# S181X.net
KiCad netlist of a schematic drawn in EAGLE
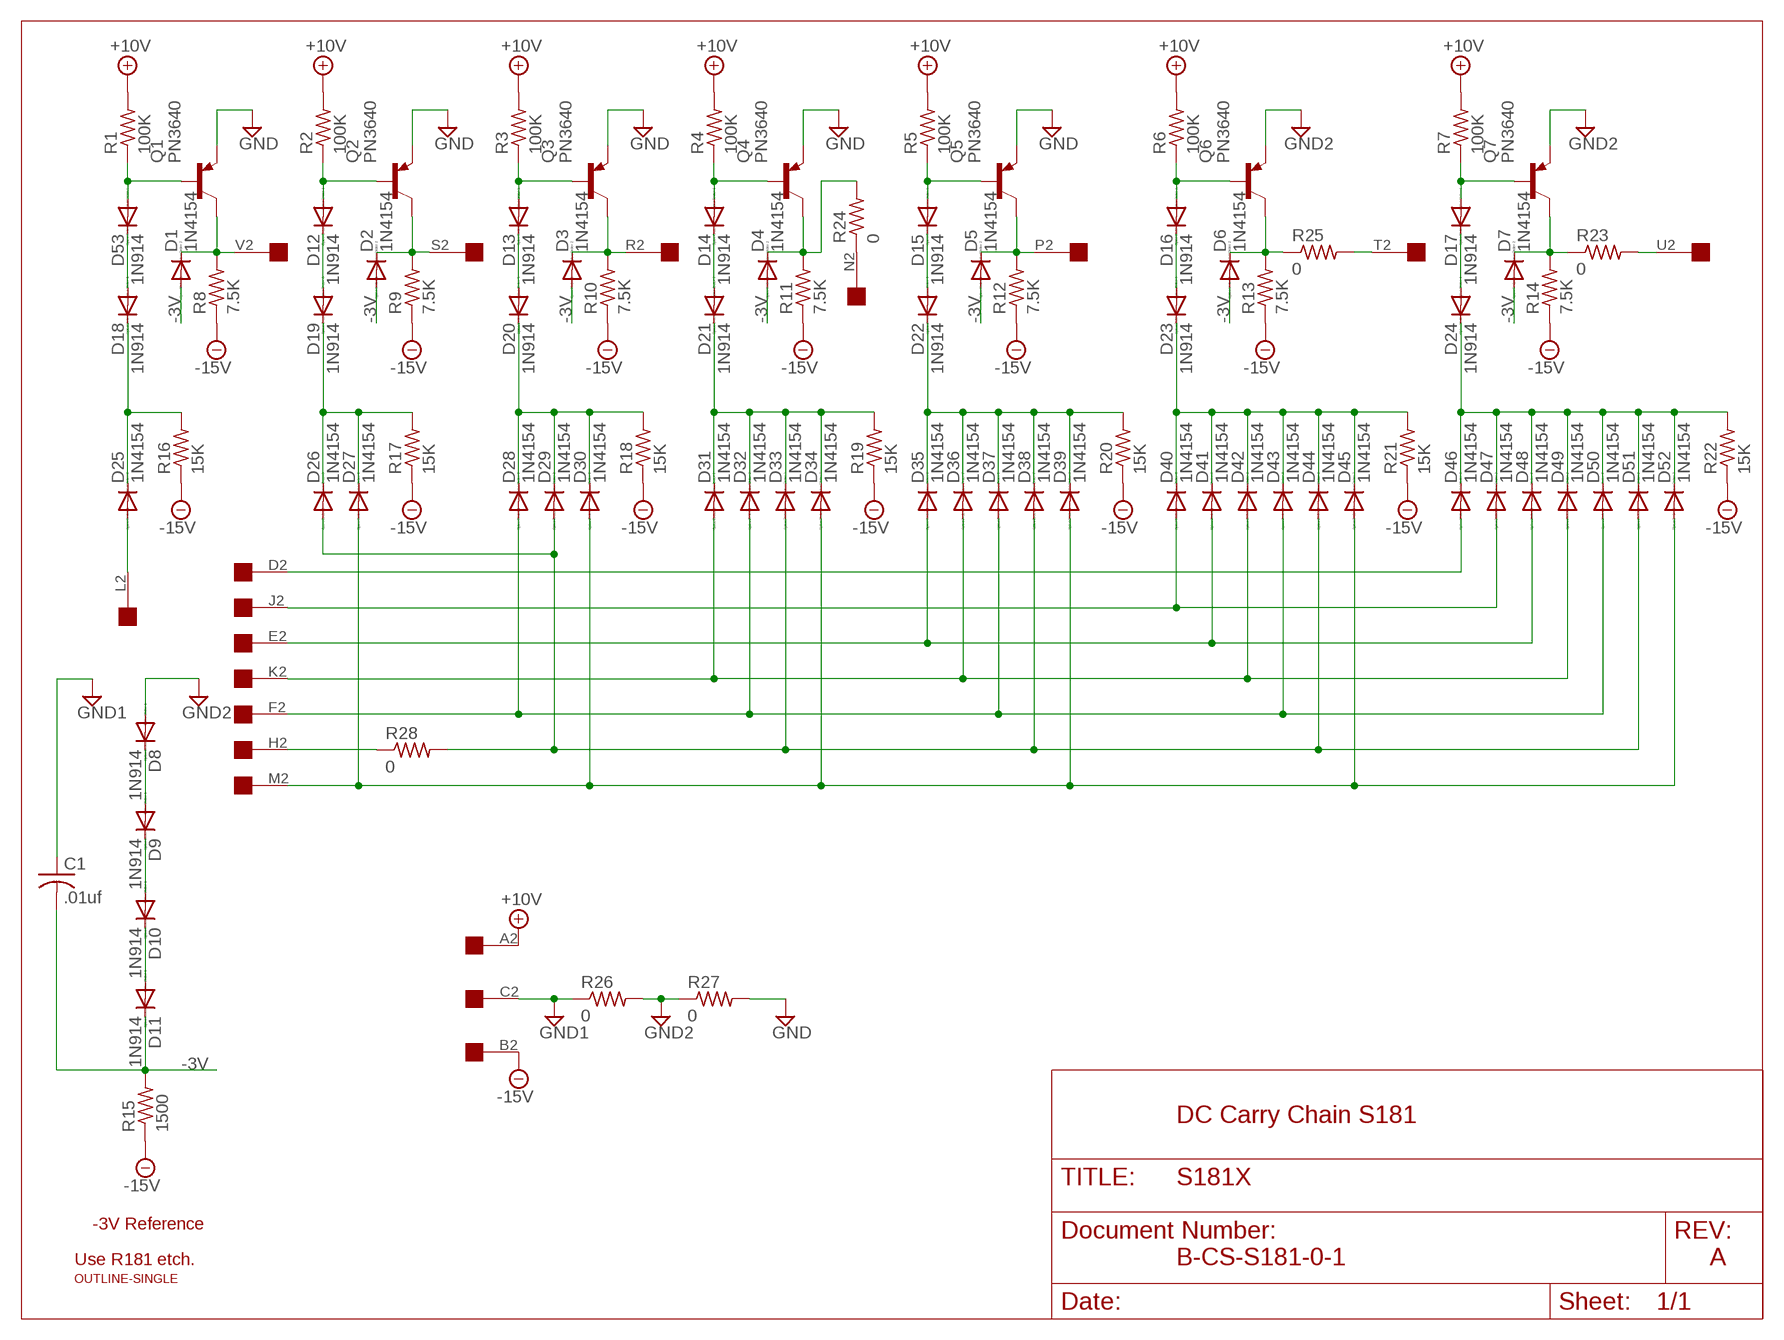
[diagram p0: schematic, sheet 1]

(export (version "E")
  (design (tool "Eeschema 10.0.6"))
  (components
    (comp (ref "C1")
      (value ".01uf")
      (footprint "eagle-import:C050-025X075")
      (libsource (lib "eagle-import") (part "C-US050-025X075"))
    )
    (comp (ref "D1")
      (value "1N4154")
      (footprint "eagle-import:DO35-10")
      (libsource (lib "eagle-import") (part "1N4148DO35-10"))
    )
    (comp (ref "D2")
      (value "1N4154")
      (footprint "eagle-import:DO35-10")
      (libsource (lib "eagle-import") (part "1N4148DO35-10"))
    )
    (comp (ref "D3")
      (value "1N4154")
      (footprint "eagle-import:DO35-10")
      (libsource (lib "eagle-import") (part "1N4148DO35-10"))
    )
    (comp (ref "D4")
      (value "1N4154")
      (footprint "eagle-import:DO35-10")
      (libsource (lib "eagle-import") (part "1N4148DO35-10"))
    )
    (comp (ref "D5")
      (value "1N4154")
      (footprint "eagle-import:DO35-10")
      (libsource (lib "eagle-import") (part "1N4148DO35-10"))
    )
    (comp (ref "D6")
      (value "1N4154")
      (footprint "eagle-import:DO35-10")
      (libsource (lib "eagle-import") (part "1N4148DO35-10"))
    )
    (comp (ref "D7")
      (value "1N4154")
      (footprint "eagle-import:DO35-10")
      (libsource (lib "eagle-import") (part "1N4148DO35-10"))
    )
    (comp (ref "D8")
      (value "1N914")
      (footprint "eagle-import:DO35-10")
      (libsource (lib "eagle-import") (part "1N4148DO35-10"))
    )
    (comp (ref "D9")
      (value "1N914")
      (footprint "eagle-import:DO35-10")
      (libsource (lib "eagle-import") (part "1N4148DO35-10"))
    )
    (comp (ref "D10")
      (value "1N914")
      (footprint "eagle-import:DO35-10")
      (libsource (lib "eagle-import") (part "1N4148DO35-10"))
    )
    (comp (ref "D11")
      (value "1N914")
      (footprint "eagle-import:DO35-10")
      (libsource (lib "eagle-import") (part "1N4148DO35-10"))
    )
    (comp (ref "D12")
      (value "1N914")
      (footprint "eagle-import:DO35-10")
      (libsource (lib "eagle-import") (part "1N4148DO35-10"))
    )
    (comp (ref "D13")
      (value "1N914")
      (footprint "eagle-import:DO35-10")
      (libsource (lib "eagle-import") (part "1N4148DO35-10"))
    )
    (comp (ref "D14")
      (value "1N914")
      (footprint "eagle-import:DO35-10")
      (libsource (lib "eagle-import") (part "1N4148DO35-10"))
    )
    (comp (ref "D15")
      (value "1N914")
      (footprint "eagle-import:DO35-10")
      (libsource (lib "eagle-import") (part "1N4148DO35-10"))
    )
    (comp (ref "D16")
      (value "1N914")
      (footprint "eagle-import:DO35-10")
      (libsource (lib "eagle-import") (part "1N4148DO35-10"))
    )
    (comp (ref "D17")
      (value "1N914")
      (footprint "eagle-import:DO35-10")
      (libsource (lib "eagle-import") (part "1N4148DO35-10"))
    )
    (comp (ref "D18")
      (value "1N914")
      (footprint "eagle-import:DO35-10")
      (libsource (lib "eagle-import") (part "1N4148DO35-10"))
    )
    (comp (ref "D19")
      (value "1N914")
      (footprint "eagle-import:DO35-10")
      (libsource (lib "eagle-import") (part "1N4148DO35-10"))
    )
    (comp (ref "D20")
      (value "1N914")
      (footprint "eagle-import:DO35-10")
      (libsource (lib "eagle-import") (part "1N4148DO35-10"))
    )
    (comp (ref "D21")
      (value "1N914")
      (footprint "eagle-import:DO35-10")
      (libsource (lib "eagle-import") (part "1N4148DO35-10"))
    )
    (comp (ref "D22")
      (value "1N914")
      (footprint "eagle-import:DO35-10")
      (libsource (lib "eagle-import") (part "1N4148DO35-10"))
    )
    (comp (ref "D23")
      (value "1N914")
      (footprint "eagle-import:DO35-10")
      (libsource (lib "eagle-import") (part "1N4148DO35-10"))
    )
    (comp (ref "D24")
      (value "1N914")
      (footprint "eagle-import:DO35-10")
      (libsource (lib "eagle-import") (part "1N4148DO35-10"))
    )
    (comp (ref "D25")
      (value "1N4154")
      (footprint "eagle-import:DO35-10")
      (libsource (lib "eagle-import") (part "1N4148DO35-10"))
    )
    (comp (ref "D26")
      (value "1N4154")
      (footprint "eagle-import:DO35-10")
      (libsource (lib "eagle-import") (part "1N4148DO35-10"))
    )
    (comp (ref "D27")
      (value "1N4154")
      (footprint "eagle-import:DO35-10")
      (libsource (lib "eagle-import") (part "1N4148DO35-10"))
    )
    (comp (ref "D28")
      (value "1N4154")
      (footprint "eagle-import:DO35-10")
      (libsource (lib "eagle-import") (part "1N4148DO35-10"))
    )
    (comp (ref "D29")
      (value "1N4154")
      (footprint "eagle-import:DO35-10")
      (libsource (lib "eagle-import") (part "1N4148DO35-10"))
    )
    (comp (ref "D30")
      (value "1N4154")
      (footprint "eagle-import:DO35-10")
      (libsource (lib "eagle-import") (part "1N4148DO35-10"))
    )
    (comp (ref "D31")
      (value "1N4154")
      (footprint "eagle-import:DO35-10")
      (libsource (lib "eagle-import") (part "1N4148DO35-10"))
    )
    (comp (ref "D32")
      (value "1N4154")
      (footprint "eagle-import:DO35-10")
      (libsource (lib "eagle-import") (part "1N4148DO35-10"))
    )
    (comp (ref "D33")
      (value "1N4154")
      (footprint "eagle-import:DO35-10")
      (libsource (lib "eagle-import") (part "1N4148DO35-10"))
    )
    (comp (ref "D34")
      (value "1N4154")
      (footprint "eagle-import:DO35-10")
      (libsource (lib "eagle-import") (part "1N4148DO35-10"))
    )
    (comp (ref "D35")
      (value "1N4154")
      (footprint "eagle-import:DO35-10")
      (libsource (lib "eagle-import") (part "1N4148DO35-10"))
    )
    (comp (ref "D36")
      (value "1N4154")
      (footprint "eagle-import:DO35-10")
      (libsource (lib "eagle-import") (part "1N4148DO35-10"))
    )
    (comp (ref "D37")
      (value "1N4154")
      (footprint "eagle-import:DO35-10")
      (libsource (lib "eagle-import") (part "1N4148DO35-10"))
    )
    (comp (ref "D38")
      (value "1N4154")
      (footprint "eagle-import:DO35-10")
      (libsource (lib "eagle-import") (part "1N4148DO35-10"))
    )
    (comp (ref "D39")
      (value "1N4154")
      (footprint "eagle-import:DO35-10")
      (libsource (lib "eagle-import") (part "1N4148DO35-10"))
    )
    (comp (ref "D40")
      (value "1N4154")
      (footprint "eagle-import:DO35-10")
      (libsource (lib "eagle-import") (part "1N4148DO35-10"))
    )
    (comp (ref "D41")
      (value "1N4154")
      (footprint "eagle-import:DO35-10")
      (libsource (lib "eagle-import") (part "1N4148DO35-10"))
    )
    (comp (ref "D42")
      (value "1N4154")
      (footprint "eagle-import:DO35-10")
      (libsource (lib "eagle-import") (part "1N4148DO35-10"))
    )
    (comp (ref "D43")
      (value "1N4154")
      (footprint "eagle-import:DO35-10")
      (libsource (lib "eagle-import") (part "1N4148DO35-10"))
    )
    (comp (ref "D44")
      (value "1N4154")
      (footprint "eagle-import:DO35-10")
      (libsource (lib "eagle-import") (part "1N4148DO35-10"))
    )
    (comp (ref "D45")
      (value "1N4154")
      (footprint "eagle-import:DO35-10")
      (libsource (lib "eagle-import") (part "1N4148DO35-10"))
    )
    (comp (ref "D46")
      (value "1N4154")
      (footprint "eagle-import:DO35-10")
      (libsource (lib "eagle-import") (part "1N4148DO35-10"))
    )
    (comp (ref "D47")
      (value "1N4154")
      (footprint "eagle-import:DO35-10")
      (libsource (lib "eagle-import") (part "1N4148DO35-10"))
    )
    (comp (ref "D48")
      (value "1N4154")
      (footprint "eagle-import:DO35-10")
      (libsource (lib "eagle-import") (part "1N4148DO35-10"))
    )
    (comp (ref "D49")
      (value "1N4154")
      (footprint "eagle-import:DO35-10")
      (libsource (lib "eagle-import") (part "1N4148DO35-10"))
    )
    (comp (ref "D50")
      (value "1N4154")
      (footprint "eagle-import:DO35-10")
      (libsource (lib "eagle-import") (part "1N4148DO35-10"))
    )
    (comp (ref "D51")
      (value "1N4154")
      (footprint "eagle-import:DO35-10")
      (libsource (lib "eagle-import") (part "1N4148DO35-10"))
    )
    (comp (ref "D52")
      (value "1N4154")
      (footprint "eagle-import:DO35-10")
      (libsource (lib "eagle-import") (part "1N4148DO35-10"))
    )
    (comp (ref "D53")
      (value "1N914")
      (footprint "eagle-import:DO35-10")
      (libsource (lib "eagle-import") (part "1N4148DO35-10"))
    )
    (comp (ref "Q1")
      (value "PN3640")
      (footprint "eagle-import:TO39")
      (libsource (lib "eagle-import") (part "2N3637"))
    )
    (comp (ref "Q2")
      (value "PN3640")
      (footprint "eagle-import:TO39")
      (libsource (lib "eagle-import") (part "2N3637"))
    )
    (comp (ref "Q3")
      (value "PN3640")
      (footprint "eagle-import:TO39")
      (libsource (lib "eagle-import") (part "2N3637"))
    )
    (comp (ref "Q4")
      (value "PN3640")
      (footprint "eagle-import:TO39")
      (libsource (lib "eagle-import") (part "2N3637"))
    )
    (comp (ref "Q5")
      (value "PN3640")
      (footprint "eagle-import:TO39")
      (libsource (lib "eagle-import") (part "2N3637"))
    )
    (comp (ref "Q6")
      (value "PN3640")
      (footprint "eagle-import:TO39")
      (libsource (lib "eagle-import") (part "2N3637"))
    )
    (comp (ref "Q7")
      (value "PN3640")
      (footprint "eagle-import:TO39")
      (libsource (lib "eagle-import") (part "2N3637"))
    )
    (comp (ref "R1")
      (value "100K")
      (footprint "eagle-import:0207_10")
      (libsource (lib "eagle-import") (part "R-US_0207/10"))
    )
    (comp (ref "R2")
      (value "100K")
      (footprint "eagle-import:0207_10")
      (libsource (lib "eagle-import") (part "R-US_0207/10"))
    )
    (comp (ref "R3")
      (value "100K")
      (footprint "eagle-import:0207_10")
      (libsource (lib "eagle-import") (part "R-US_0207/10"))
    )
    (comp (ref "R4")
      (value "100K")
      (footprint "eagle-import:0207_10")
      (libsource (lib "eagle-import") (part "R-US_0207/10"))
    )
    (comp (ref "R5")
      (value "100K")
      (footprint "eagle-import:0207_10")
      (libsource (lib "eagle-import") (part "R-US_0207/10"))
    )
    (comp (ref "R6")
      (value "100K")
      (footprint "eagle-import:0207_10")
      (libsource (lib "eagle-import") (part "R-US_0207/10"))
    )
    (comp (ref "R7")
      (value "100K")
      (footprint "eagle-import:0207_10")
      (libsource (lib "eagle-import") (part "R-US_0207/10"))
    )
    (comp (ref "R8")
      (value "7.5K")
      (footprint "eagle-import:0207_10")
      (libsource (lib "eagle-import") (part "R-US_0207/10"))
    )
    (comp (ref "R9")
      (value "7.5K")
      (footprint "eagle-import:0207_10")
      (libsource (lib "eagle-import") (part "R-US_0207/10"))
    )
    (comp (ref "R10")
      (value "7.5K")
      (footprint "eagle-import:0207_10")
      (libsource (lib "eagle-import") (part "R-US_0207/10"))
    )
    (comp (ref "R11")
      (value "7.5K")
      (footprint "eagle-import:0207_10")
      (libsource (lib "eagle-import") (part "R-US_0207/10"))
    )
    (comp (ref "R12")
      (value "7.5K")
      (footprint "eagle-import:0207_10")
      (libsource (lib "eagle-import") (part "R-US_0207/10"))
    )
    (comp (ref "R13")
      (value "7.5K")
      (footprint "eagle-import:0207_10")
      (libsource (lib "eagle-import") (part "R-US_0207/10"))
    )
    (comp (ref "R14")
      (value "7.5K")
      (footprint "eagle-import:0207_10")
      (libsource (lib "eagle-import") (part "R-US_0207/10"))
    )
    (comp (ref "R15")
      (value "1500")
      (footprint "eagle-import:0207_10")
      (libsource (lib "eagle-import") (part "R-US_0207/10"))
    )
    (comp (ref "R16")
      (value "15K")
      (footprint "eagle-import:0207_10")
      (libsource (lib "eagle-import") (part "R-US_0207/10"))
    )
    (comp (ref "R17")
      (value "15K")
      (footprint "eagle-import:0207_10")
      (libsource (lib "eagle-import") (part "R-US_0207/10"))
    )
    (comp (ref "R18")
      (value "15K")
      (footprint "eagle-import:0207_10")
      (libsource (lib "eagle-import") (part "R-US_0207/10"))
    )
    (comp (ref "R19")
      (value "15K")
      (footprint "eagle-import:0207_10")
      (libsource (lib "eagle-import") (part "R-US_0207/10"))
    )
    (comp (ref "R20")
      (value "15K")
      (footprint "eagle-import:0207_10")
      (libsource (lib "eagle-import") (part "R-US_0207/10"))
    )
    (comp (ref "R21")
      (value "15K")
      (footprint "eagle-import:0207_10")
      (libsource (lib "eagle-import") (part "R-US_0207/10"))
    )
    (comp (ref "R22")
      (value "15K")
      (footprint "eagle-import:0207_10")
      (libsource (lib "eagle-import") (part "R-US_0207/10"))
    )
    (comp (ref "R23")
      (value "0")
      (footprint "eagle-import:0207_10")
      (libsource (lib "eagle-import") (part "R-US_0207/10"))
    )
    (comp (ref "R24")
      (value "0")
      (footprint "eagle-import:0207_10")
      (libsource (lib "eagle-import") (part "R-US_0207/10"))
    )
    (comp (ref "R25")
      (value "0")
      (footprint "eagle-import:0207_10")
      (libsource (lib "eagle-import") (part "R-US_0207/10"))
    )
    (comp (ref "R26")
      (value "0")
      (footprint "eagle-import:0207_10")
      (libsource (lib "eagle-import") (part "R-US_0207/10"))
    )
    (comp (ref "R27")
      (value "0")
      (footprint "eagle-import:0207_10")
      (libsource (lib "eagle-import") (part "R-US_0207/10"))
    )
    (comp (ref "R28")
      (value "0")
      (footprint "eagle-import:0207_10")
      (libsource (lib "eagle-import") (part "R-US_0207/10"))
    )
    (comp (ref "U$1")
      (value "OUTLINE-SINGLE")
      (footprint "eagle-import:SINGLE")
      (libsource (lib "eagle-import") (part "OUTLINE-SINGLE"))
    )
    (comp (ref "U$2")
      (value "EDGE-1")
      (footprint "eagle-import:EDGE-CON1")
      (libsource (lib "eagle-import") (part "EDGE-1"))
    )
  )
  (nets
    (net (code "1") (name "+10V") (class "Default")
      (node (ref "R1") (pin "2") (pinfunction "2_2") (pintype "passive"))
      (node (ref "R2") (pin "2") (pinfunction "2_2") (pintype "passive"))
      (node (ref "R3") (pin "2") (pinfunction "2_2") (pintype "passive"))
      (node (ref "R4") (pin "2") (pinfunction "2_2") (pintype "passive"))
      (node (ref "R5") (pin "2") (pinfunction "2_2") (pintype "passive"))
      (node (ref "R6") (pin "2") (pinfunction "2_2") (pintype "passive"))
      (node (ref "R7") (pin "2") (pinfunction "2_2") (pintype "passive"))
      (node (ref "U$2") (pin "A2") (pinfunction "1_A2") (pintype "bidirectional"))
    )
    (net (code "2") (name "-15V") (class "Default")
      (node (ref "R10") (pin "1") (pinfunction "1_1") (pintype "passive"))
      (node (ref "R11") (pin "1") (pinfunction "1_1") (pintype "passive"))
      (node (ref "R12") (pin "1") (pinfunction "1_1") (pintype "passive"))
      (node (ref "R13") (pin "1") (pinfunction "1_1") (pintype "passive"))
      (node (ref "R14") (pin "1") (pinfunction "1_1") (pintype "passive"))
      (node (ref "R15") (pin "1") (pinfunction "1_1") (pintype "passive"))
      (node (ref "R16") (pin "1") (pinfunction "1_1") (pintype "passive"))
      (node (ref "R17") (pin "1") (pinfunction "1_1") (pintype "passive"))
      (node (ref "R18") (pin "1") (pinfunction "1_1") (pintype "passive"))
      (node (ref "R19") (pin "1") (pinfunction "1_1") (pintype "passive"))
      (node (ref "R20") (pin "1") (pinfunction "1_1") (pintype "passive"))
      (node (ref "R21") (pin "1") (pinfunction "1_1") (pintype "passive"))
      (node (ref "R22") (pin "1") (pinfunction "1_1") (pintype "passive"))
      (node (ref "R8") (pin "1") (pinfunction "1_1") (pintype "passive"))
      (node (ref "R9") (pin "1") (pinfunction "1_1") (pintype "passive"))
      (node (ref "U$2") (pin "B2") (pinfunction "1_B2") (pintype "bidirectional"))
    )
    (net (code "3") (name "/-3V") (class "Default")
      (node (ref "C1") (pin "2") (pinfunction "2_2") (pintype "passive"))
      (node (ref "D1") (pin "A") (pinfunction "A_A") (pintype "passive"))
      (node (ref "D11") (pin "C") (pinfunction "C_C") (pintype "passive"))
      (node (ref "D2") (pin "A") (pinfunction "A_A") (pintype "passive"))
      (node (ref "D3") (pin "A") (pinfunction "A_A") (pintype "passive"))
      (node (ref "D4") (pin "A") (pinfunction "A_A") (pintype "passive"))
      (node (ref "D5") (pin "A") (pinfunction "A_A") (pintype "passive"))
      (node (ref "D6") (pin "A") (pinfunction "A_A") (pintype "passive"))
      (node (ref "D7") (pin "A") (pinfunction "A_A") (pintype "passive"))
      (node (ref "R15") (pin "2") (pinfunction "2_2") (pintype "passive"))
    )
    (net (code "4") (name "GND") (class "Default")
      (node (ref "Q1") (pin "1") (pinfunction "E_1") (pintype "passive"))
      (node (ref "Q2") (pin "1") (pinfunction "E_1") (pintype "passive"))
      (node (ref "Q3") (pin "1") (pinfunction "E_1") (pintype "passive"))
      (node (ref "Q4") (pin "1") (pinfunction "E_1") (pintype "passive"))
      (node (ref "Q5") (pin "1") (pinfunction "E_1") (pintype "passive"))
      (node (ref "R27") (pin "2") (pinfunction "2_2") (pintype "passive"))
    )
    (net (code "5") (name "GND1") (class "Default")
      (node (ref "C1") (pin "1") (pinfunction "1_1") (pintype "passive"))
      (node (ref "R26") (pin "1") (pinfunction "1_1") (pintype "passive"))
      (node (ref "U$2") (pin "C2") (pinfunction "1_C2") (pintype "bidirectional"))
    )
    (net (code "6") (name "GND2") (class "Default")
      (node (ref "D8") (pin "A") (pinfunction "A_A") (pintype "passive"))
      (node (ref "Q6") (pin "1") (pinfunction "E_1") (pintype "passive"))
      (node (ref "Q7") (pin "1") (pinfunction "E_1") (pintype "passive"))
      (node (ref "R26") (pin "2") (pinfunction "2_2") (pintype "passive"))
      (node (ref "R27") (pin "1") (pinfunction "1_1") (pintype "passive"))
    )
    (net (code "7") (name "Net-(D8-PadC)") (class "Default")
      (node (ref "D8") (pin "C") (pinfunction "C_C") (pintype "passive"))
      (node (ref "D9") (pin "A") (pinfunction "A_A") (pintype "passive"))
    )
    (net (code "8") (name "Net-(D10-PadA)") (class "Default")
      (node (ref "D10") (pin "A") (pinfunction "A_A") (pintype "passive"))
      (node (ref "D9") (pin "C") (pinfunction "C_C") (pintype "passive"))
    )
    (net (code "9") (name "Net-(D10-PadC)") (class "Default")
      (node (ref "D10") (pin "C") (pinfunction "C_C") (pintype "passive"))
      (node (ref "D11") (pin "A") (pinfunction "A_A") (pintype "passive"))
    )
    (net (code "10") (name "Net-(D12-PadC)") (class "Default")
      (node (ref "D12") (pin "C") (pinfunction "C_C") (pintype "passive"))
      (node (ref "D19") (pin "A") (pinfunction "A_A") (pintype "passive"))
    )
    (net (code "11") (name "Net-(D13-PadC)") (class "Default")
      (node (ref "D13") (pin "C") (pinfunction "C_C") (pintype "passive"))
      (node (ref "D20") (pin "A") (pinfunction "A_A") (pintype "passive"))
    )
    (net (code "12") (name "Net-(D14-PadC)") (class "Default")
      (node (ref "D14") (pin "C") (pinfunction "C_C") (pintype "passive"))
      (node (ref "D21") (pin "A") (pinfunction "A_A") (pintype "passive"))
    )
    (net (code "13") (name "Net-(D15-PadC)") (class "Default")
      (node (ref "D15") (pin "C") (pinfunction "C_C") (pintype "passive"))
      (node (ref "D22") (pin "A") (pinfunction "A_A") (pintype "passive"))
    )
    (net (code "14") (name "Net-(D16-PadC)") (class "Default")
      (node (ref "D16") (pin "C") (pinfunction "C_C") (pintype "passive"))
      (node (ref "D23") (pin "A") (pinfunction "A_A") (pintype "passive"))
    )
    (net (code "15") (name "Net-(D17-PadC)") (class "Default")
      (node (ref "D17") (pin "C") (pinfunction "C_C") (pintype "passive"))
      (node (ref "D24") (pin "A") (pinfunction "A_A") (pintype "passive"))
    )
    (net (code "16") (name "Net-(D18-PadA)") (class "Default")
      (node (ref "D18") (pin "A") (pinfunction "A_A") (pintype "passive"))
      (node (ref "D53") (pin "C") (pinfunction "C_C") (pintype "passive"))
    )
    (net (code "17") (name "Net-(D18-PadC)") (class "Default")
      (node (ref "D18") (pin "C") (pinfunction "C_C") (pintype "passive"))
      (node (ref "D25") (pin "C") (pinfunction "C_C") (pintype "passive"))
      (node (ref "R16") (pin "2") (pinfunction "2_2") (pintype "passive"))
    )
    (net (code "18") (name "Net-(D19-PadC)") (class "Default")
      (node (ref "D19") (pin "C") (pinfunction "C_C") (pintype "passive"))
      (node (ref "D26") (pin "C") (pinfunction "C_C") (pintype "passive"))
      (node (ref "D27") (pin "C") (pinfunction "C_C") (pintype "passive"))
      (node (ref "R17") (pin "2") (pinfunction "2_2") (pintype "passive"))
    )
    (net (code "19") (name "Net-(D20-PadC)") (class "Default")
      (node (ref "D20") (pin "C") (pinfunction "C_C") (pintype "passive"))
      (node (ref "D28") (pin "C") (pinfunction "C_C") (pintype "passive"))
      (node (ref "D29") (pin "C") (pinfunction "C_C") (pintype "passive"))
      (node (ref "D30") (pin "C") (pinfunction "C_C") (pintype "passive"))
      (node (ref "R18") (pin "2") (pinfunction "2_2") (pintype "passive"))
    )
    (net (code "20") (name "Net-(D21-PadC)") (class "Default")
      (node (ref "D21") (pin "C") (pinfunction "C_C") (pintype "passive"))
      (node (ref "D31") (pin "C") (pinfunction "C_C") (pintype "passive"))
      (node (ref "D32") (pin "C") (pinfunction "C_C") (pintype "passive"))
      (node (ref "D33") (pin "C") (pinfunction "C_C") (pintype "passive"))
      (node (ref "D34") (pin "C") (pinfunction "C_C") (pintype "passive"))
      (node (ref "R19") (pin "2") (pinfunction "2_2") (pintype "passive"))
    )
    (net (code "21") (name "Net-(D22-PadC)") (class "Default")
      (node (ref "D22") (pin "C") (pinfunction "C_C") (pintype "passive"))
      (node (ref "D35") (pin "C") (pinfunction "C_C") (pintype "passive"))
      (node (ref "D36") (pin "C") (pinfunction "C_C") (pintype "passive"))
      (node (ref "D37") (pin "C") (pinfunction "C_C") (pintype "passive"))
      (node (ref "D38") (pin "C") (pinfunction "C_C") (pintype "passive"))
      (node (ref "D39") (pin "C") (pinfunction "C_C") (pintype "passive"))
      (node (ref "R20") (pin "2") (pinfunction "2_2") (pintype "passive"))
    )
    (net (code "22") (name "Net-(D23-PadC)") (class "Default")
      (node (ref "D23") (pin "C") (pinfunction "C_C") (pintype "passive"))
      (node (ref "D40") (pin "C") (pinfunction "C_C") (pintype "passive"))
      (node (ref "D41") (pin "C") (pinfunction "C_C") (pintype "passive"))
      (node (ref "D42") (pin "C") (pinfunction "C_C") (pintype "passive"))
      (node (ref "D43") (pin "C") (pinfunction "C_C") (pintype "passive"))
      (node (ref "D44") (pin "C") (pinfunction "C_C") (pintype "passive"))
      (node (ref "D45") (pin "C") (pinfunction "C_C") (pintype "passive"))
      (node (ref "R21") (pin "2") (pinfunction "2_2") (pintype "passive"))
    )
    (net (code "23") (name "Net-(D24-PadC)") (class "Default")
      (node (ref "D24") (pin "C") (pinfunction "C_C") (pintype "passive"))
      (node (ref "D46") (pin "C") (pinfunction "C_C") (pintype "passive"))
      (node (ref "D47") (pin "C") (pinfunction "C_C") (pintype "passive"))
      (node (ref "D48") (pin "C") (pinfunction "C_C") (pintype "passive"))
      (node (ref "D49") (pin "C") (pinfunction "C_C") (pintype "passive"))
      (node (ref "D50") (pin "C") (pinfunction "C_C") (pintype "passive"))
      (node (ref "D51") (pin "C") (pinfunction "C_C") (pintype "passive"))
      (node (ref "D52") (pin "C") (pinfunction "C_C") (pintype "passive"))
      (node (ref "R22") (pin "2") (pinfunction "2_2") (pintype "passive"))
    )
    (net (code "24") (name "Net-(D26-PadA)") (class "Default")
      (node (ref "D26") (pin "A") (pinfunction "A_A") (pintype "passive"))
      (node (ref "D29") (pin "A") (pinfunction "A_A") (pintype "passive"))
      (node (ref "D33") (pin "A") (pinfunction "A_A") (pintype "passive"))
      (node (ref "D38") (pin "A") (pinfunction "A_A") (pintype "passive"))
      (node (ref "D44") (pin "A") (pinfunction "A_A") (pintype "passive"))
      (node (ref "D51") (pin "A") (pinfunction "A_A") (pintype "passive"))
      (node (ref "R28") (pin "2") (pinfunction "2_2") (pintype "passive"))
    )
    (net (code "25") (name "Net-(Q1-B)") (class "Default")
      (node (ref "D53") (pin "A") (pinfunction "A_A") (pintype "passive"))
      (node (ref "Q1") (pin "2") (pinfunction "B_2") (pintype "passive"))
      (node (ref "R1") (pin "1") (pinfunction "1_1") (pintype "passive"))
    )
    (net (code "26") (name "Net-(Q1-C)") (class "Default")
      (node (ref "D1") (pin "C") (pinfunction "C_C") (pintype "passive"))
      (node (ref "Q1") (pin "3") (pinfunction "C_3") (pintype "passive"))
      (node (ref "R8") (pin "2") (pinfunction "2_2") (pintype "passive"))
      (node (ref "U$2") (pin "V2") (pinfunction "1_V2") (pintype "bidirectional"))
    )
    (net (code "27") (name "Net-(Q2-B)") (class "Default")
      (node (ref "D12") (pin "A") (pinfunction "A_A") (pintype "passive"))
      (node (ref "Q2") (pin "2") (pinfunction "B_2") (pintype "passive"))
      (node (ref "R2") (pin "1") (pinfunction "1_1") (pintype "passive"))
    )
    (net (code "28") (name "Net-(Q2-C)") (class "Default")
      (node (ref "D2") (pin "C") (pinfunction "C_C") (pintype "passive"))
      (node (ref "Q2") (pin "3") (pinfunction "C_3") (pintype "passive"))
      (node (ref "R9") (pin "2") (pinfunction "2_2") (pintype "passive"))
      (node (ref "U$2") (pin "S2") (pinfunction "1_S2") (pintype "bidirectional"))
    )
    (net (code "29") (name "Net-(Q3-B)") (class "Default")
      (node (ref "D13") (pin "A") (pinfunction "A_A") (pintype "passive"))
      (node (ref "Q3") (pin "2") (pinfunction "B_2") (pintype "passive"))
      (node (ref "R3") (pin "1") (pinfunction "1_1") (pintype "passive"))
    )
    (net (code "30") (name "Net-(Q3-C)") (class "Default")
      (node (ref "D3") (pin "C") (pinfunction "C_C") (pintype "passive"))
      (node (ref "Q3") (pin "3") (pinfunction "C_3") (pintype "passive"))
      (node (ref "R10") (pin "2") (pinfunction "2_2") (pintype "passive"))
      (node (ref "U$2") (pin "R2") (pinfunction "1_R2") (pintype "bidirectional"))
    )
    (net (code "31") (name "Net-(Q4-B)") (class "Default")
      (node (ref "D14") (pin "A") (pinfunction "A_A") (pintype "passive"))
      (node (ref "Q4") (pin "2") (pinfunction "B_2") (pintype "passive"))
      (node (ref "R4") (pin "1") (pinfunction "1_1") (pintype "passive"))
    )
    (net (code "32") (name "Net-(Q4-C)") (class "Default")
      (node (ref "D4") (pin "C") (pinfunction "C_C") (pintype "passive"))
      (node (ref "Q4") (pin "3") (pinfunction "C_3") (pintype "passive"))
      (node (ref "R11") (pin "2") (pinfunction "2_2") (pintype "passive"))
      (node (ref "R24") (pin "2") (pinfunction "2_2") (pintype "passive"))
    )
    (net (code "33") (name "Net-(Q5-B)") (class "Default")
      (node (ref "D15") (pin "A") (pinfunction "A_A") (pintype "passive"))
      (node (ref "Q5") (pin "2") (pinfunction "B_2") (pintype "passive"))
      (node (ref "R5") (pin "1") (pinfunction "1_1") (pintype "passive"))
    )
    (net (code "34") (name "Net-(Q5-C)") (class "Default")
      (node (ref "D5") (pin "C") (pinfunction "C_C") (pintype "passive"))
      (node (ref "Q5") (pin "3") (pinfunction "C_3") (pintype "passive"))
      (node (ref "R12") (pin "2") (pinfunction "2_2") (pintype "passive"))
      (node (ref "U$2") (pin "P2") (pinfunction "1_P2") (pintype "bidirectional"))
    )
    (net (code "35") (name "Net-(Q6-B)") (class "Default")
      (node (ref "D16") (pin "A") (pinfunction "A_A") (pintype "passive"))
      (node (ref "Q6") (pin "2") (pinfunction "B_2") (pintype "passive"))
      (node (ref "R6") (pin "1") (pinfunction "1_1") (pintype "passive"))
    )
    (net (code "36") (name "Net-(Q6-C)") (class "Default")
      (node (ref "D6") (pin "C") (pinfunction "C_C") (pintype "passive"))
      (node (ref "Q6") (pin "3") (pinfunction "C_3") (pintype "passive"))
      (node (ref "R13") (pin "2") (pinfunction "2_2") (pintype "passive"))
      (node (ref "R25") (pin "1") (pinfunction "1_1") (pintype "passive"))
    )
    (net (code "37") (name "Net-(Q7-B)") (class "Default")
      (node (ref "D17") (pin "A") (pinfunction "A_A") (pintype "passive"))
      (node (ref "Q7") (pin "2") (pinfunction "B_2") (pintype "passive"))
      (node (ref "R7") (pin "1") (pinfunction "1_1") (pintype "passive"))
    )
    (net (code "38") (name "Net-(Q7-C)") (class "Default")
      (node (ref "D7") (pin "C") (pinfunction "C_C") (pintype "passive"))
      (node (ref "Q7") (pin "3") (pinfunction "C_3") (pintype "passive"))
      (node (ref "R14") (pin "2") (pinfunction "2_2") (pintype "passive"))
      (node (ref "R23") (pin "1") (pinfunction "1_1") (pintype "passive"))
    )
    (net (code "39") (name "Net-(U$2D-1)") (class "Default")
      (node (ref "D46") (pin "A") (pinfunction "A_A") (pintype "passive"))
      (node (ref "U$2") (pin "D2") (pinfunction "1_D2") (pintype "bidirectional"))
    )
    (net (code "40") (name "Net-(U$2E-1)") (class "Default")
      (node (ref "D35") (pin "A") (pinfunction "A_A") (pintype "passive"))
      (node (ref "D41") (pin "A") (pinfunction "A_A") (pintype "passive"))
      (node (ref "D48") (pin "A") (pinfunction "A_A") (pintype "passive"))
      (node (ref "U$2") (pin "E2") (pinfunction "1_E2") (pintype "bidirectional"))
    )
    (net (code "41") (name "Net-(U$2F-1)") (class "Default")
      (node (ref "D28") (pin "A") (pinfunction "A_A") (pintype "passive"))
      (node (ref "D32") (pin "A") (pinfunction "A_A") (pintype "passive"))
      (node (ref "D37") (pin "A") (pinfunction "A_A") (pintype "passive"))
      (node (ref "D43") (pin "A") (pinfunction "A_A") (pintype "passive"))
      (node (ref "D50") (pin "A") (pinfunction "A_A") (pintype "passive"))
      (node (ref "U$2") (pin "F2") (pinfunction "1_F2") (pintype "bidirectional"))
    )
    (net (code "42") (name "Net-(U$2G-1)") (class "Default")
      (node (ref "R28") (pin "1") (pinfunction "1_1") (pintype "passive"))
      (node (ref "U$2") (pin "H2") (pinfunction "1_H2") (pintype "bidirectional"))
    )
    (net (code "43") (name "Net-(U$2H-1)") (class "Default")
      (node (ref "D40") (pin "A") (pinfunction "A_A") (pintype "passive"))
      (node (ref "D47") (pin "A") (pinfunction "A_A") (pintype "passive"))
      (node (ref "U$2") (pin "J2") (pinfunction "1_J2") (pintype "bidirectional"))
    )
    (net (code "44") (name "Net-(U$2I-1)") (class "Default")
      (node (ref "D31") (pin "A") (pinfunction "A_A") (pintype "passive"))
      (node (ref "D36") (pin "A") (pinfunction "A_A") (pintype "passive"))
      (node (ref "D42") (pin "A") (pinfunction "A_A") (pintype "passive"))
      (node (ref "D49") (pin "A") (pinfunction "A_A") (pintype "passive"))
      (node (ref "U$2") (pin "K2") (pinfunction "1_K2") (pintype "bidirectional"))
    )
    (net (code "45") (name "Net-(U$2J-1)") (class "Default")
      (node (ref "D25") (pin "A") (pinfunction "A_A") (pintype "passive"))
      (node (ref "U$2") (pin "L2") (pinfunction "1_L2") (pintype "bidirectional"))
    )
    (net (code "46") (name "Net-(U$2K-1)") (class "Default")
      (node (ref "D27") (pin "A") (pinfunction "A_A") (pintype "passive"))
      (node (ref "D30") (pin "A") (pinfunction "A_A") (pintype "passive"))
      (node (ref "D34") (pin "A") (pinfunction "A_A") (pintype "passive"))
      (node (ref "D39") (pin "A") (pinfunction "A_A") (pintype "passive"))
      (node (ref "D45") (pin "A") (pinfunction "A_A") (pintype "passive"))
      (node (ref "D52") (pin "A") (pinfunction "A_A") (pintype "passive"))
      (node (ref "U$2") (pin "M2") (pinfunction "1_M2") (pintype "bidirectional"))
    )
    (net (code "47") (name "Net-(U$2L-1)") (class "Default")
      (node (ref "R24") (pin "1") (pinfunction "1_1") (pintype "passive"))
      (node (ref "U$2") (pin "N2") (pinfunction "1_N2") (pintype "bidirectional"))
    )
    (net (code "48") (name "Net-(U$2P-1)") (class "Default")
      (node (ref "R25") (pin "2") (pinfunction "2_2") (pintype "passive"))
      (node (ref "U$2") (pin "T2") (pinfunction "1_T2") (pintype "bidirectional"))
    )
    (net (code "49") (name "Net-(U$2Q-1)") (class "Default")
      (node (ref "R23") (pin "2") (pinfunction "2_2") (pintype "passive"))
      (node (ref "U$2") (pin "U2") (pinfunction "1_U2") (pintype "bidirectional"))
    )
  )
)
